# source_eagle.net
KiCad netlist of a schematic drawn in EAGLE
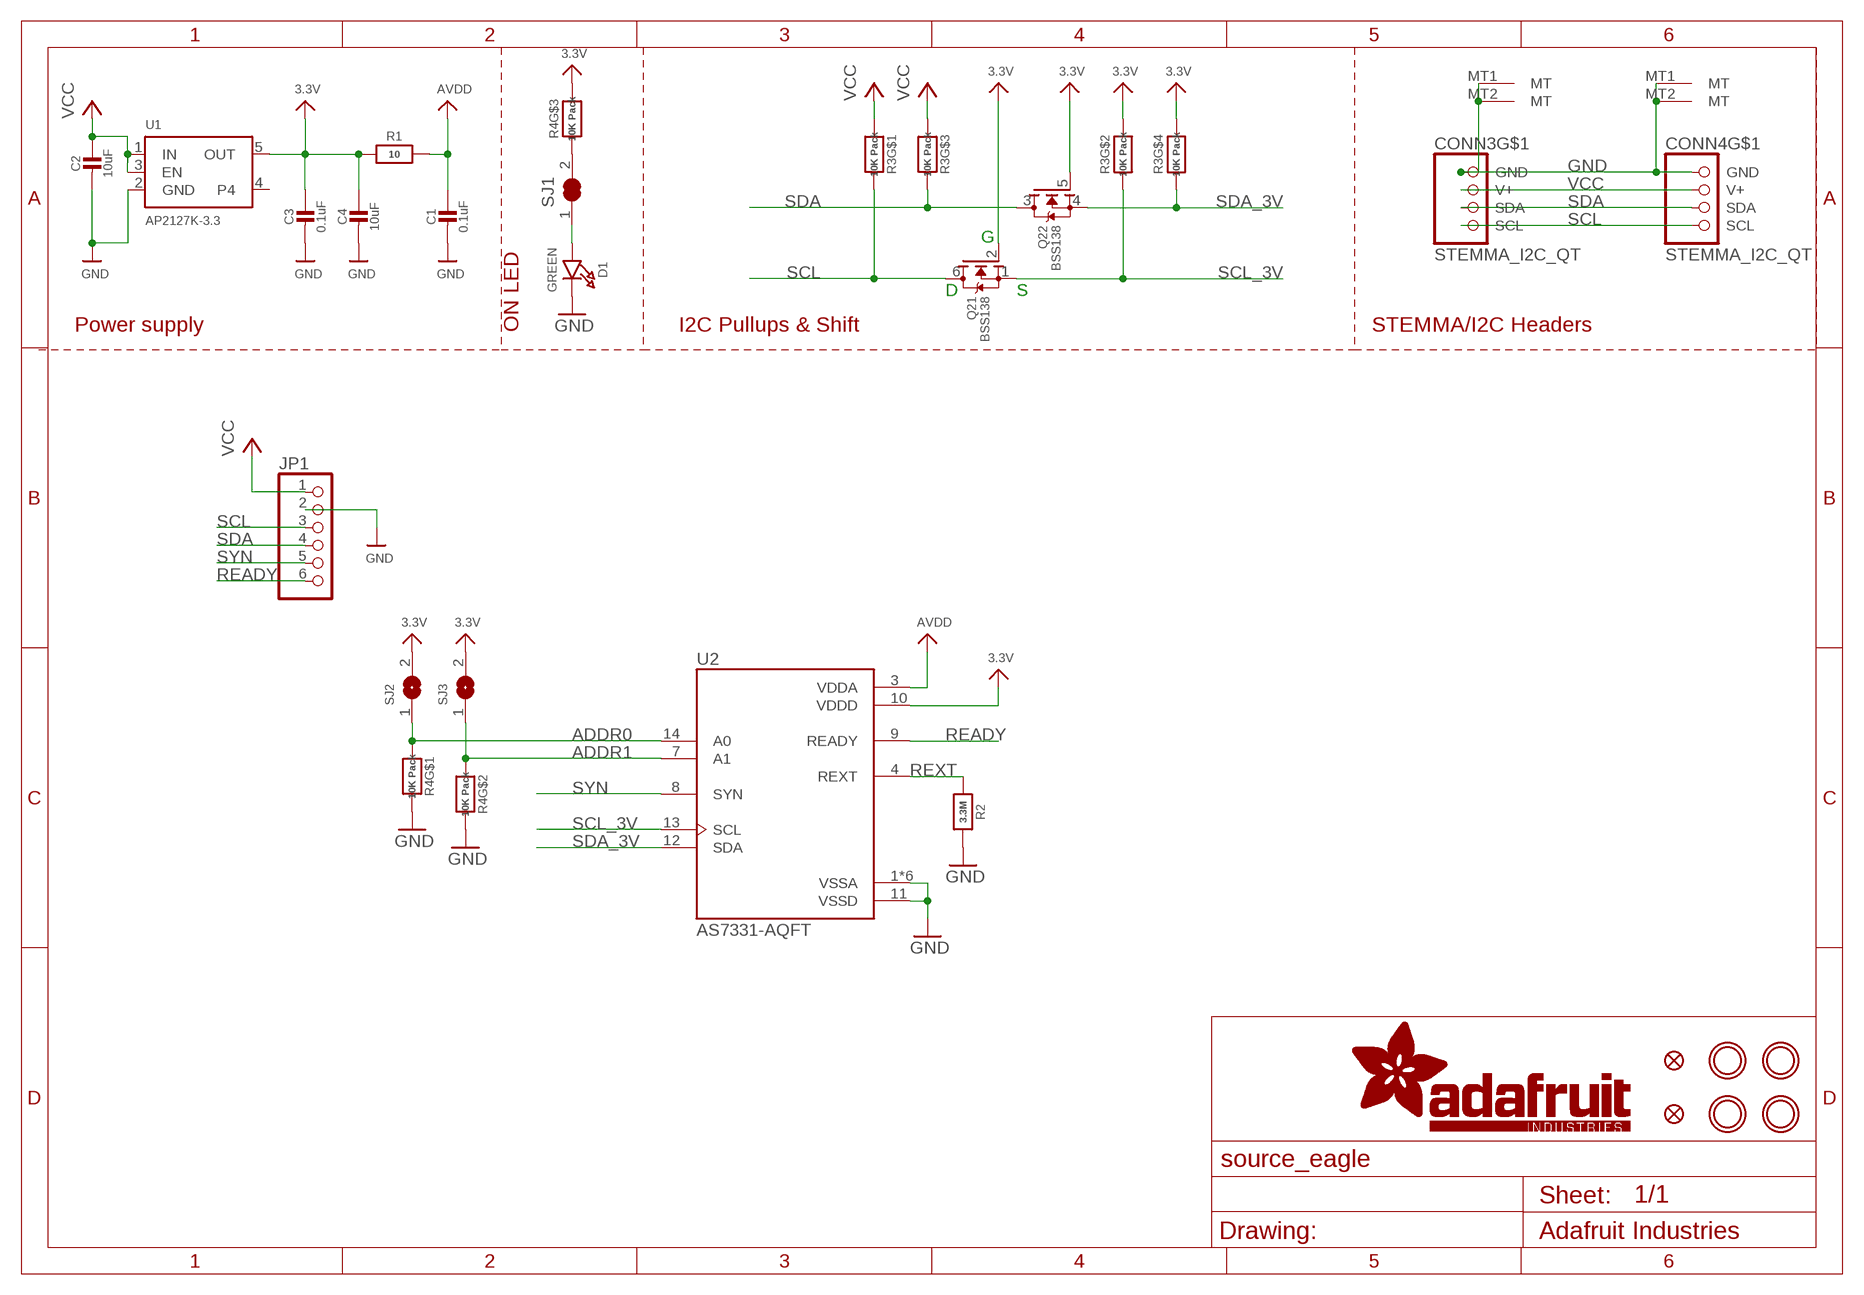
[diagram p0: schematic, sheet 1]

(export (version "E")
  (design (tool "Eeschema 10.0.6"))
  (components
    (comp (ref "C1")
      (value "0.1uF")
      (footprint "eagle-import:0603-NO")
      (libsource (lib "eagle-import") (part "CAP_CERAMIC0603_NO"))
    )
    (comp (ref "C2")
      (value "10uF")
      (footprint "eagle-import:0805-NO")
      (libsource (lib "eagle-import") (part "CAP_CERAMIC0805-NOOUTLINE"))
    )
    (comp (ref "C3")
      (value "0.1uF")
      (footprint "eagle-import:0603-NO")
      (libsource (lib "eagle-import") (part "CAP_CERAMIC0603_NO"))
    )
    (comp (ref "C4")
      (value "10uF")
      (footprint "eagle-import:0805-NO")
      (libsource (lib "eagle-import") (part "CAP_CERAMIC0805-NOOUTLINE"))
    )
    (comp (ref "CONN3")
      (value "STEMMA_I2C_QT")
      (footprint "eagle-import:JST_SH4")
      (libsource (lib "eagle-import") (part "STEMMA_I2C_QT"))
    )
    (comp (ref "CONN4")
      (value "STEMMA_I2C_QT")
      (footprint "eagle-import:JST_SH4")
      (libsource (lib "eagle-import") (part "STEMMA_I2C_QT"))
    )
    (comp (ref "D1")
      (value "GREEN")
      (footprint "eagle-import:CHIPLED_0603_NOOUTLINE")
      (libsource (lib "eagle-import") (part "LED0603_NOOUTLINE"))
    )
    (comp (ref "FID3")
      (value "FIDUCIAL_0.5MM")
      (footprint "eagle-import:FIDUCIAL_0.5MM")
      (libsource (lib "eagle-import") (part "FIDUCIAL_0.5MM"))
    )
    (comp (ref "FID4")
      (value "FIDUCIAL_0.5MM")
      (footprint "eagle-import:FIDUCIAL_0.5MM")
      (libsource (lib "eagle-import") (part "FIDUCIAL_0.5MM"))
    )
    (comp (ref "JP1")
      (value "HEADER-1X670MIL")
      (footprint "eagle-import:1X06_ROUND_70")
      (libsource (lib "eagle-import") (part "HEADER-1X670MIL"))
    )
    (comp (ref "Q2")
      (value "BSS138")
      (footprint "eagle-import:SOT363")
      (libsource (lib "eagle-import") (part "MOSFET-N_DUAL"))
    )
    (comp (ref "R1")
      (value "10")
      (footprint "eagle-import:0603-NO")
      (libsource (lib "eagle-import") (part "RESISTOR_0603_NOOUT"))
    )
    (comp (ref "R2")
      (value "3.3M")
      (footprint "eagle-import:0603-NO")
      (libsource (lib "eagle-import") (part "RESISTOR_0603_NOOUT"))
    )
    (comp (ref "R3")
      (value "10K Pack")
      (footprint "eagle-import:RESPACK_4X0603")
      (libsource (lib "eagle-import") (part "RESISTOR_4PACK"))
    )
    (comp (ref "R4")
      (value "10K Pack")
      (footprint "eagle-import:RESPACK_4X0603")
      (libsource (lib "eagle-import") (part "RESISTOR_4PACK"))
    )
    (comp (ref "SJ1")
      (value "SOLDERJUMPER_CLOSED")
      (footprint "eagle-import:SOLDERJUMPER_CLOSEDWIRE")
      (libsource (lib "eagle-import") (part "SOLDERJUMPER_CLOSED"))
    )
    (comp (ref "SJ2")
      (value "SOLDERJUMPER")
      (footprint "eagle-import:SOLDERJUMPER_ARROW_NOPASTE")
      (libsource (lib "eagle-import") (part "SOLDERJUMPER"))
    )
    (comp (ref "SJ3")
      (value "SOLDERJUMPER")
      (footprint "eagle-import:SOLDERJUMPER_ARROW_NOPASTE")
      (libsource (lib "eagle-import") (part "SOLDERJUMPER"))
    )
    (comp (ref "U$1")
      (value "MOUNTINGHOLE2.5")
      (footprint "eagle-import:MOUNTINGHOLE_2.5_PLATED")
      (libsource (lib "eagle-import") (part "MOUNTINGHOLE2.5"))
    )
    (comp (ref "U$17")
      (value "MOUNTINGHOLE2.5")
      (footprint "eagle-import:MOUNTINGHOLE_2.5_PLATED")
      (libsource (lib "eagle-import") (part "MOUNTINGHOLE2.5"))
    )
    (comp (ref "U$19")
      (value "MOUNTINGHOLE2.5")
      (footprint "eagle-import:MOUNTINGHOLE_2.5_PLATED")
      (libsource (lib "eagle-import") (part "MOUNTINGHOLE2.5"))
    )
    (comp (ref "U$21")
      (value "MOUNTINGHOLE2.5")
      (footprint "eagle-import:MOUNTINGHOLE_2.5_PLATED")
      (libsource (lib "eagle-import") (part "MOUNTINGHOLE2.5"))
    )
    (comp (ref "U1")
      (value "AP2127K-3.3")
      (footprint "eagle-import:SOT23-5")
      (libsource (lib "eagle-import") (part "VREG_SOT23-5"))
    )
    (comp (ref "U2")
      (value "AS7331-AQFT")
      (footprint "eagle-import:AS7331_SNAP")
      (fields (field (name "MF") "ams OSRAM"))
      (libsource (lib "eagle-import") (part "AS7331-AQFT"))
    )
  )
  (nets
    (net (code "1") (name "/ADDR0") (class "Default")
      (node (ref "R4") (pin "1") (pinfunction "1_1") (pintype "passive"))
      (node (ref "SJ2") (pin "1") (pinfunction "1_1") (pintype "passive"))
      (node (ref "U2") (pin "14") (pinfunction "A0_14") (pintype "input"))
    )
    (net (code "2") (name "/ADDR1") (class "Default")
      (node (ref "R4") (pin "2") (pinfunction "1_2") (pintype "passive"))
      (node (ref "SJ3") (pin "1") (pinfunction "1_1") (pintype "passive"))
      (node (ref "U2") (pin "7") (pinfunction "A1_7") (pintype "input"))
    )
    (net (code "3") (name "/READY") (class "Default")
      (node (ref "JP1") (pin "6") (pinfunction "6_6") (pintype "passive"))
      (node (ref "U2") (pin "9") (pinfunction "READY_9") (pintype "output"))
    )
    (net (code "4") (name "/REXT") (class "Default")
      (node (ref "R2") (pin "1") (pinfunction "1_1") (pintype "passive"))
      (node (ref "U2") (pin "4") (pinfunction "REXT_4") (pintype "bidirectional"))
    )
    (net (code "5") (name "/SCL") (class "Default")
      (node (ref "CONN3") (pin "4") (pinfunction "SCL_4") (pintype "passive"))
      (node (ref "CONN4") (pin "4") (pinfunction "SCL_4") (pintype "passive"))
      (node (ref "JP1") (pin "3") (pinfunction "3_3") (pintype "passive"))
      (node (ref "Q2") (pin "6") (pinfunction "D_6") (pintype "bidirectional"))
      (node (ref "R3") (pin "8") (pinfunction "2_8") (pintype "passive"))
    )
    (net (code "6") (name "/SCL_3V") (class "Default")
      (node (ref "Q2") (pin "1") (pinfunction "S_1") (pintype "bidirectional"))
      (node (ref "R3") (pin "7") (pinfunction "2_7") (pintype "passive"))
      (node (ref "U2") (pin "13") (pinfunction "SCL_13") (pintype "input"))
    )
    (net (code "7") (name "/SDA") (class "Default")
      (node (ref "CONN3") (pin "3") (pinfunction "SDA_3") (pintype "passive"))
      (node (ref "CONN4") (pin "3") (pinfunction "SDA_3") (pintype "passive"))
      (node (ref "JP1") (pin "4") (pinfunction "4_4") (pintype "passive"))
      (node (ref "Q2") (pin "3") (pinfunction "D_3") (pintype "bidirectional"))
      (node (ref "R3") (pin "6") (pinfunction "2_6") (pintype "passive"))
    )
    (net (code "8") (name "/SDA_3V") (class "Default")
      (node (ref "Q2") (pin "4") (pinfunction "S_4") (pintype "bidirectional"))
      (node (ref "R3") (pin "5") (pinfunction "2_5") (pintype "passive"))
      (node (ref "U2") (pin "12") (pinfunction "SDA_12") (pintype "bidirectional"))
    )
    (net (code "9") (name "/SYN") (class "Default")
      (node (ref "JP1") (pin "5") (pinfunction "5_5") (pintype "passive"))
      (node (ref "U2") (pin "8") (pinfunction "SYN_8") (pintype "input"))
    )
    (net (code "10") (name "3.3V") (class "Default")
      (node (ref "C3") (pin "1") (pinfunction "1_1") (pintype "passive"))
      (node (ref "C4") (pin "1") (pinfunction "1_1") (pintype "passive"))
      (node (ref "Q2") (pin "2") (pinfunction "G_2") (pintype "bidirectional"))
      (node (ref "Q2") (pin "5") (pinfunction "G_5") (pintype "bidirectional"))
      (node (ref "R1") (pin "1") (pinfunction "1_1") (pintype "passive"))
      (node (ref "R3") (pin "2") (pinfunction "1_2") (pintype "passive"))
      (node (ref "R3") (pin "4") (pinfunction "1_4") (pintype "passive"))
      (node (ref "R4") (pin "6") (pinfunction "2_6") (pintype "passive"))
      (node (ref "SJ2") (pin "2") (pinfunction "2_2") (pintype "passive"))
      (node (ref "SJ3") (pin "2") (pinfunction "2_2") (pintype "passive"))
      (node (ref "U1") (pin "5") (pinfunction "OUT_5") (pintype "power_in"))
      (node (ref "U2") (pin "10") (pinfunction "VDDD_10") (pintype "power_in"))
    )
    (net (code "11") (name "AVDD") (class "Default")
      (node (ref "C1") (pin "1") (pinfunction "1_1") (pintype "passive"))
      (node (ref "R1") (pin "2") (pinfunction "2_2") (pintype "passive"))
      (node (ref "U2") (pin "3") (pinfunction "VDDA_3") (pintype "power_in"))
    )
    (net (code "12") (name "GND") (class "Default")
      (node (ref "C1") (pin "2") (pinfunction "2_2") (pintype "passive"))
      (node (ref "C2") (pin "2") (pinfunction "2_2") (pintype "passive"))
      (node (ref "C3") (pin "2") (pinfunction "2_2") (pintype "passive"))
      (node (ref "C4") (pin "2") (pinfunction "2_2") (pintype "passive"))
      (node (ref "CONN3") (pin "1") (pinfunction "GND_1") (pintype "passive"))
      (node (ref "CONN3") (pin "MT1") (pinfunction "MT_MT1") (pintype "bidirectional"))
      (node (ref "CONN3") (pin "MT2") (pinfunction "MT_MT2") (pintype "bidirectional"))
      (node (ref "CONN4") (pin "1") (pinfunction "GND_1") (pintype "passive"))
      (node (ref "CONN4") (pin "MT1") (pinfunction "MT_MT1") (pintype "bidirectional"))
      (node (ref "CONN4") (pin "MT2") (pinfunction "MT_MT2") (pintype "bidirectional"))
      (node (ref "D1") (pin "C") (pinfunction "C_C") (pintype "passive"))
      (node (ref "JP1") (pin "2") (pinfunction "2_2") (pintype "passive"))
      (node (ref "R2") (pin "2") (pinfunction "2_2") (pintype "passive"))
      (node (ref "R4") (pin "7") (pinfunction "2_7") (pintype "passive"))
      (node (ref "R4") (pin "8") (pinfunction "2_8") (pintype "passive"))
      (node (ref "U1") (pin "2") (pinfunction "GND_2") (pintype "power_in"))
      (node (ref "U2") (pin "1") (pinfunction "VSSA_1") (pintype "power_in"))
      (node (ref "U2") (pin "11") (pinfunction "VSSD_11") (pintype "power_in"))
      (node (ref "U2") (pin "15") (pinfunction "VSSA_15") (pintype "power_in"))
      (node (ref "U2") (pin "16") (pinfunction "VSSA_16") (pintype "power_in"))
      (node (ref "U2") (pin "2") (pinfunction "VSSA_2") (pintype "power_in"))
      (node (ref "U2") (pin "5") (pinfunction "VSSA_5") (pintype "power_in"))
      (node (ref "U2") (pin "6") (pinfunction "VSSA_6") (pintype "power_in"))
    )
    (net (code "13") (name "Net-(D1-PadA)") (class "Default")
      (node (ref "D1") (pin "A") (pinfunction "A_A") (pintype "passive"))
      (node (ref "SJ1") (pin "1") (pinfunction "1_1") (pintype "passive"))
    )
    (net (code "14") (name "Net-(R4C-1)") (class "Default")
      (node (ref "R4") (pin "3") (pinfunction "1_3") (pintype "passive"))
      (node (ref "SJ1") (pin "2") (pinfunction "2_2") (pintype "passive"))
    )
    (net (code "15") (name "VCC") (class "Default")
      (node (ref "C2") (pin "1") (pinfunction "1_1") (pintype "passive"))
      (node (ref "CONN3") (pin "2") (pinfunction "V+_2") (pintype "passive"))
      (node (ref "CONN4") (pin "2") (pinfunction "V+_2") (pintype "passive"))
      (node (ref "JP1") (pin "1") (pinfunction "1_1") (pintype "passive"))
      (node (ref "R3") (pin "1") (pinfunction "1_1") (pintype "passive"))
      (node (ref "R3") (pin "3") (pinfunction "1_3") (pintype "passive"))
      (node (ref "U1") (pin "1") (pinfunction "IN_1") (pintype "power_in"))
      (node (ref "U1") (pin "3") (pinfunction "EN_3") (pintype "input"))
    )
    (net (code "16") (name "unconnected-(U1-P4-Pad4)") (class "Default")
      (node (ref "U1") (pin "4") (pinfunction "P4_4") (pintype "bidirectional"))
    )
  )
)
